# Adafruit_Non-Latching_Relay_Breakout.net
KiCad netlist of a schematic drawn in EAGLE
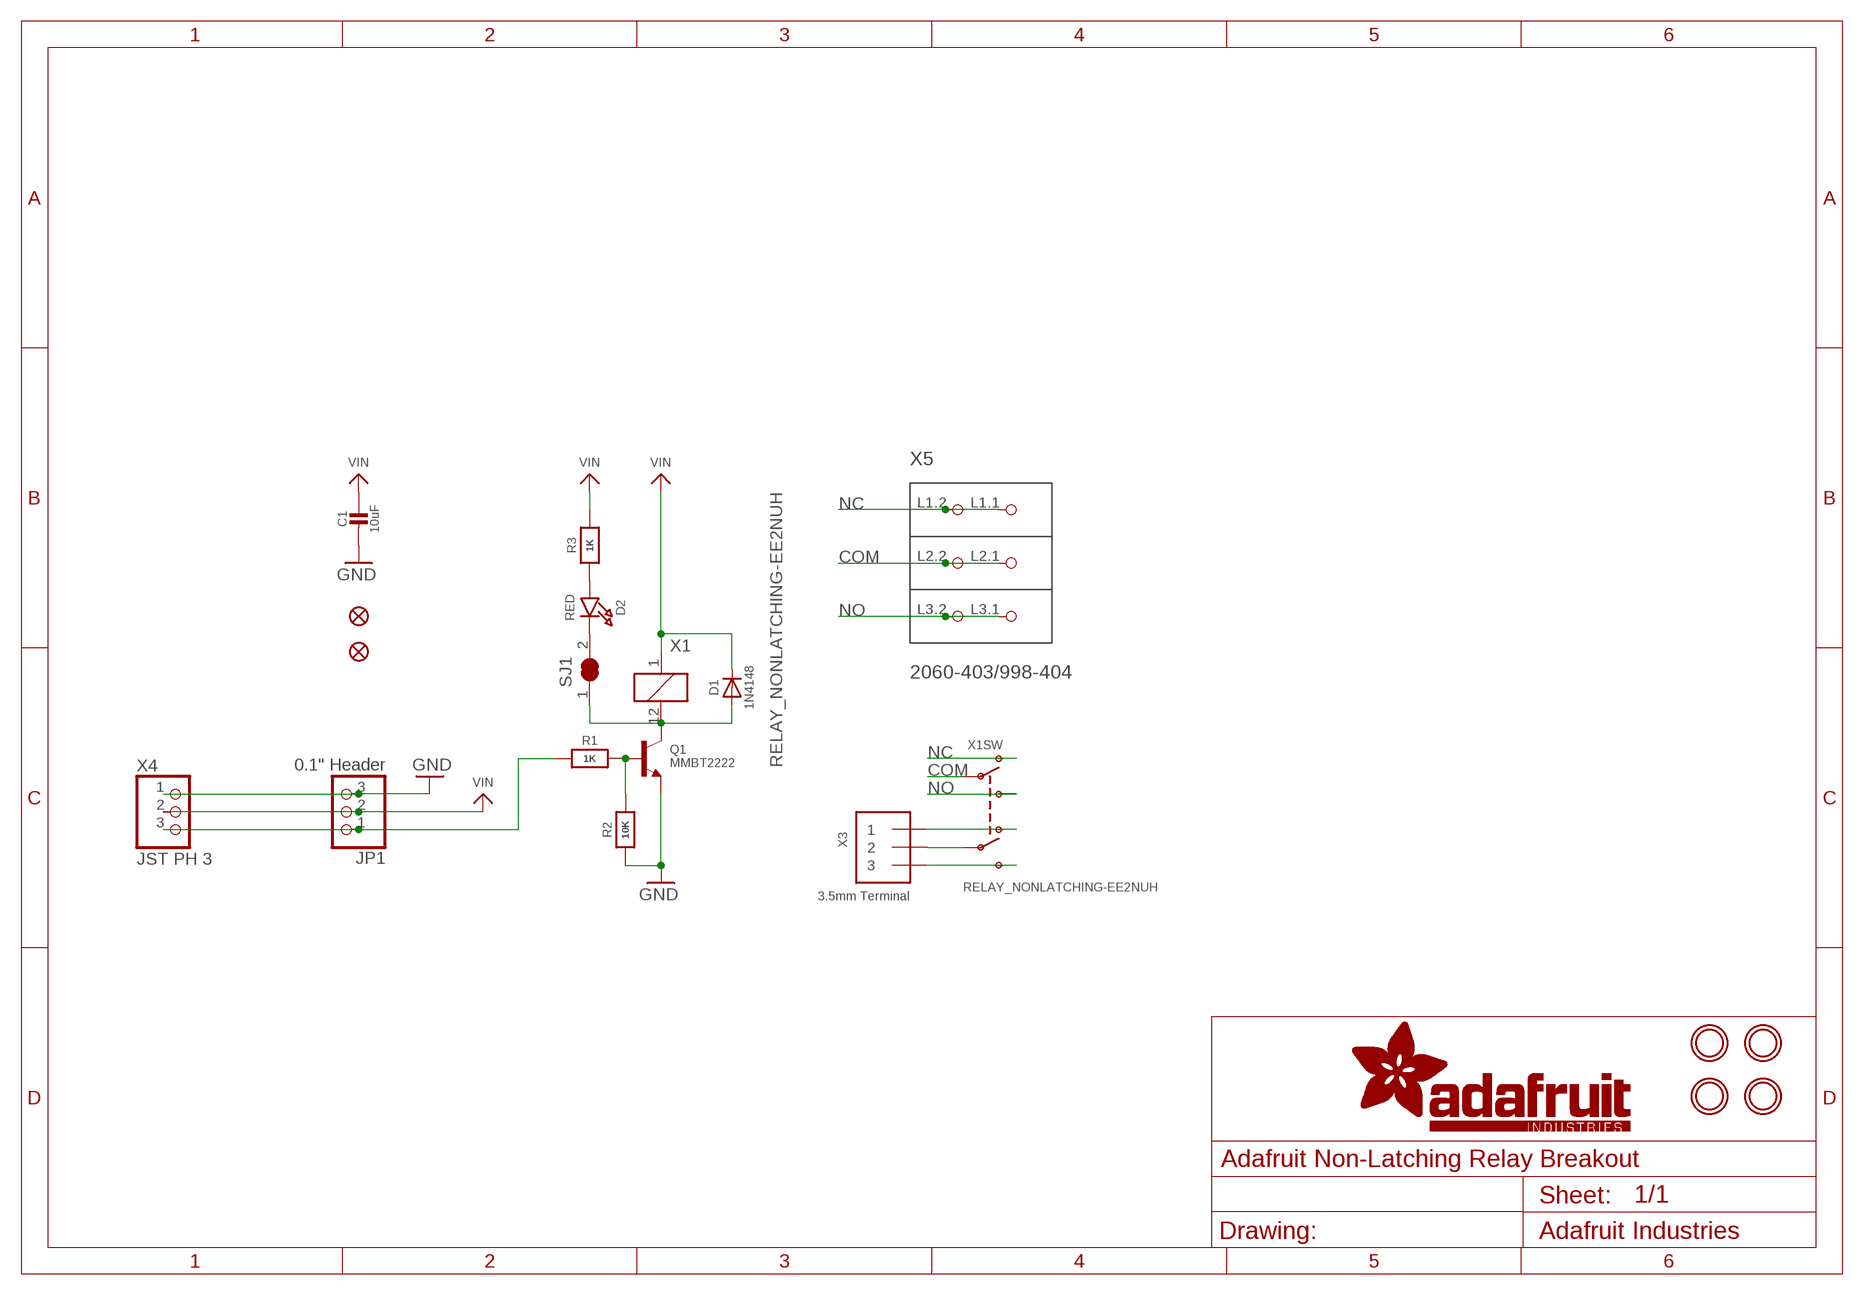
[diagram p0: schematic, sheet 1]

(export (version "E")
  (design (tool "Eeschema 10.0.6"))
  (components
    (comp (ref "C1")
      (value "10uF")
      (footprint "eagle-import:0805-NO")
      (libsource (lib "eagle-import") (part "CAP_CERAMIC0805-NOOUTLINE"))
    )
    (comp (ref "D1")
      (value "1N4148")
      (footprint "eagle-import:SOD-323")
      (libsource (lib "eagle-import") (part "DIODESOD-323"))
    )
    (comp (ref "D2")
      (value "RED")
      (footprint "eagle-import:CHIPLED_0805_NOOUTLINE")
      (libsource (lib "eagle-import") (part "LED0805_NOOUTLINE"))
    )
    (comp (ref "FID2")
      (value "FIDUCIAL_1MM")
      (footprint "eagle-import:FIDUCIAL_1MM")
      (libsource (lib "eagle-import") (part "FIDUCIAL_1MM"))
    )
    (comp (ref "FID3")
      (value "FIDUCIAL_1MM")
      (footprint "eagle-import:FIDUCIAL_1MM")
      (libsource (lib "eagle-import") (part "FIDUCIAL_1MM"))
    )
    (comp (ref "JP1")
      (value "0.1\" Header")
      (footprint "eagle-import:1X03_OVAL")
      (libsource (lib "eagle-import") (part "HEADER-1X3"))
    )
    (comp (ref "Q1")
      (value "MMBT2222")
      (footprint "eagle-import:SOT23-R")
      (libsource (lib "eagle-import") (part "TRANSISTOR_NPN"))
    )
    (comp (ref "R1")
      (value "1K")
      (footprint "eagle-import:0603-NO")
      (libsource (lib "eagle-import") (part "RESISTOR_0603_NOOUT"))
    )
    (comp (ref "R2")
      (value "10K")
      (footprint "eagle-import:0603-NO")
      (libsource (lib "eagle-import") (part "RESISTOR_0603_NOOUT"))
    )
    (comp (ref "R3")
      (value "1K")
      (footprint "eagle-import:0603-NO")
      (libsource (lib "eagle-import") (part "RESISTOR_0603_NOOUT"))
    )
    (comp (ref "SJ1")
      (value "SOLDERJUMPER_CLOSED")
      (footprint "eagle-import:SOLDERJUMPER_CLOSEDWIRE")
      (libsource (lib "eagle-import") (part "SOLDERJUMPER_CLOSED"))
    )
    (comp (ref "U$1")
      (value "MOUNTINGHOLE2.5")
      (footprint "eagle-import:MOUNTINGHOLE_2.5_PLATED")
      (libsource (lib "eagle-import") (part "MOUNTINGHOLE2.5"))
    )
    (comp (ref "U$8")
      (value "MOUNTINGHOLE2.5")
      (footprint "eagle-import:MOUNTINGHOLE_2.5_PLATED")
      (libsource (lib "eagle-import") (part "MOUNTINGHOLE2.5"))
    )
    (comp (ref "U$9")
      (value "MOUNTINGHOLE2.5")
      (footprint "eagle-import:MOUNTINGHOLE_2.5_PLATED")
      (libsource (lib "eagle-import") (part "MOUNTINGHOLE2.5"))
    )
    (comp (ref "U$10")
      (value "MOUNTINGHOLE2.5")
      (footprint "eagle-import:MOUNTINGHOLE_2.5_PLATED")
      (libsource (lib "eagle-import") (part "MOUNTINGHOLE2.5"))
    )
    (comp (ref "X1")
      (value "RELAY_NONLATCHING-EE2NUH")
      (footprint "eagle-import:RELAY_EE2_NOLATCH")
      (libsource (lib "eagle-import") (part "RELAY_NONLATCHING-EE2NUH"))
    )
    (comp (ref "X3")
      (value "3.5mm Terminal")
      (footprint "eagle-import:TERMBLOCK_1X3-3.5MM")
      (libsource (lib "eagle-import") (part "TERMBLOCK_1X3"))
    )
    (comp (ref "X4")
      (value "JST PH 3")
      (footprint "eagle-import:JSTPH3")
      (libsource (lib "eagle-import") (part "CON_JST_PH_3PIN"))
    )
    (comp (ref "X5")
      (value "2060-403/998-404")
      (footprint "eagle-import:P-2060-403_998-404")
      (libsource (lib "eagle-import") (part "2060-403/998-404"))
    )
  )
  (nets
    (net (code "1") (name "/COM") (class "Default")
      (node (ref "X1") (pin "9") (pinfunction "P1_9") (pintype "passive"))
      (node (ref "X5") (pin "L2.1") (pinfunction "P2.1_L2.1") (pintype "bidirectional"))
      (node (ref "X5") (pin "L2.2") (pinfunction "P2.2_L2.2") (pintype "bidirectional"))
    )
    (net (code "2") (name "/NC") (class "Default")
      (node (ref "X1") (pin "10") (pinfunction "O1_10") (pintype "passive"))
      (node (ref "X5") (pin "L1.1") (pinfunction "P1.1_L1.1") (pintype "bidirectional"))
      (node (ref "X5") (pin "L1.2") (pinfunction "P1.2_L1.2") (pintype "bidirectional"))
    )
    (net (code "3") (name "/NO") (class "Default")
      (node (ref "X1") (pin "8") (pinfunction "S1_8") (pintype "passive"))
      (node (ref "X5") (pin "L3.1") (pinfunction "P3.1_L3.1") (pintype "bidirectional"))
      (node (ref "X5") (pin "L3.2") (pinfunction "P3.2_L3.2") (pintype "bidirectional"))
    )
    (net (code "4") (name "GND") (class "Default")
      (node (ref "C1") (pin "2") (pinfunction "2_2") (pintype "passive"))
      (node (ref "JP1") (pin "3") (pinfunction "3_3") (pintype "passive"))
      (node (ref "Q1") (pin "2") (pinfunction "E_2") (pintype "passive"))
      (node (ref "R2") (pin "1") (pinfunction "1_1") (pintype "passive"))
      (node (ref "X4") (pin "1") (pinfunction "1_1") (pintype "passive"))
    )
    (net (code "5") (name "Net-(D2-PadA)") (class "Default")
      (node (ref "D2") (pin "A") (pinfunction "A_A") (pintype "passive"))
      (node (ref "R3") (pin "1") (pinfunction "1_1") (pintype "passive"))
    )
    (net (code "6") (name "Net-(D2-PadC)") (class "Default")
      (node (ref "D2") (pin "C") (pinfunction "C_C") (pintype "passive"))
      (node (ref "SJ1") (pin "2") (pinfunction "2_2") (pintype "passive"))
    )
    (net (code "7") (name "Net-(JP1-Pad1)") (class "Default")
      (node (ref "JP1") (pin "1") (pinfunction "1_1") (pintype "passive"))
      (node (ref "R1") (pin "1") (pinfunction "1_1") (pintype "passive"))
      (node (ref "X4") (pin "3") (pinfunction "3_3") (pintype "passive"))
    )
    (net (code "8") (name "Net-(Q1-B)") (class "Default")
      (node (ref "Q1") (pin "1") (pinfunction "B_1") (pintype "passive"))
      (node (ref "R1") (pin "2") (pinfunction "2_2") (pintype "passive"))
      (node (ref "R2") (pin "2") (pinfunction "2_2") (pintype "passive"))
    )
    (net (code "9") (name "Net-(Q1-C)") (class "Default")
      (node (ref "D1") (pin "A") (pinfunction "A_A") (pintype "passive"))
      (node (ref "Q1") (pin "3") (pinfunction "C_3") (pintype "passive"))
      (node (ref "SJ1") (pin "1") (pinfunction "1_1") (pintype "passive"))
      (node (ref "X1") (pin "12") (pinfunction "2_12") (pintype "passive"))
    )
    (net (code "10") (name "Net-(X1B-O2)") (class "Default")
      (node (ref "X1") (pin "3") (pinfunction "O2_3") (pintype "passive"))
      (node (ref "X3") (pin "1") (pinfunction "1_1") (pintype "passive"))
    )
    (net (code "11") (name "Net-(X1B-P2)") (class "Default")
      (node (ref "X1") (pin "4") (pinfunction "P2_4") (pintype "passive"))
      (node (ref "X3") (pin "2") (pinfunction "2_2") (pintype "passive"))
    )
    (net (code "12") (name "Net-(X1B-S2)") (class "Default")
      (node (ref "X1") (pin "5") (pinfunction "S2_5") (pintype "passive"))
      (node (ref "X3") (pin "3") (pinfunction "3_3") (pintype "passive"))
    )
    (net (code "13") (name "VIN") (class "Default")
      (node (ref "C1") (pin "1") (pinfunction "1_1") (pintype "passive"))
      (node (ref "D1") (pin "C") (pinfunction "C_C") (pintype "passive"))
      (node (ref "JP1") (pin "2") (pinfunction "2_2") (pintype "passive"))
      (node (ref "R3") (pin "2") (pinfunction "2_2") (pintype "passive"))
      (node (ref "X1") (pin "1") (pinfunction "1_1") (pintype "passive"))
      (node (ref "X4") (pin "2") (pinfunction "2_2") (pintype "passive"))
    )
  )
)
